# imu_shield.net
KiCad netlist of a schematic drawn in EAGLE
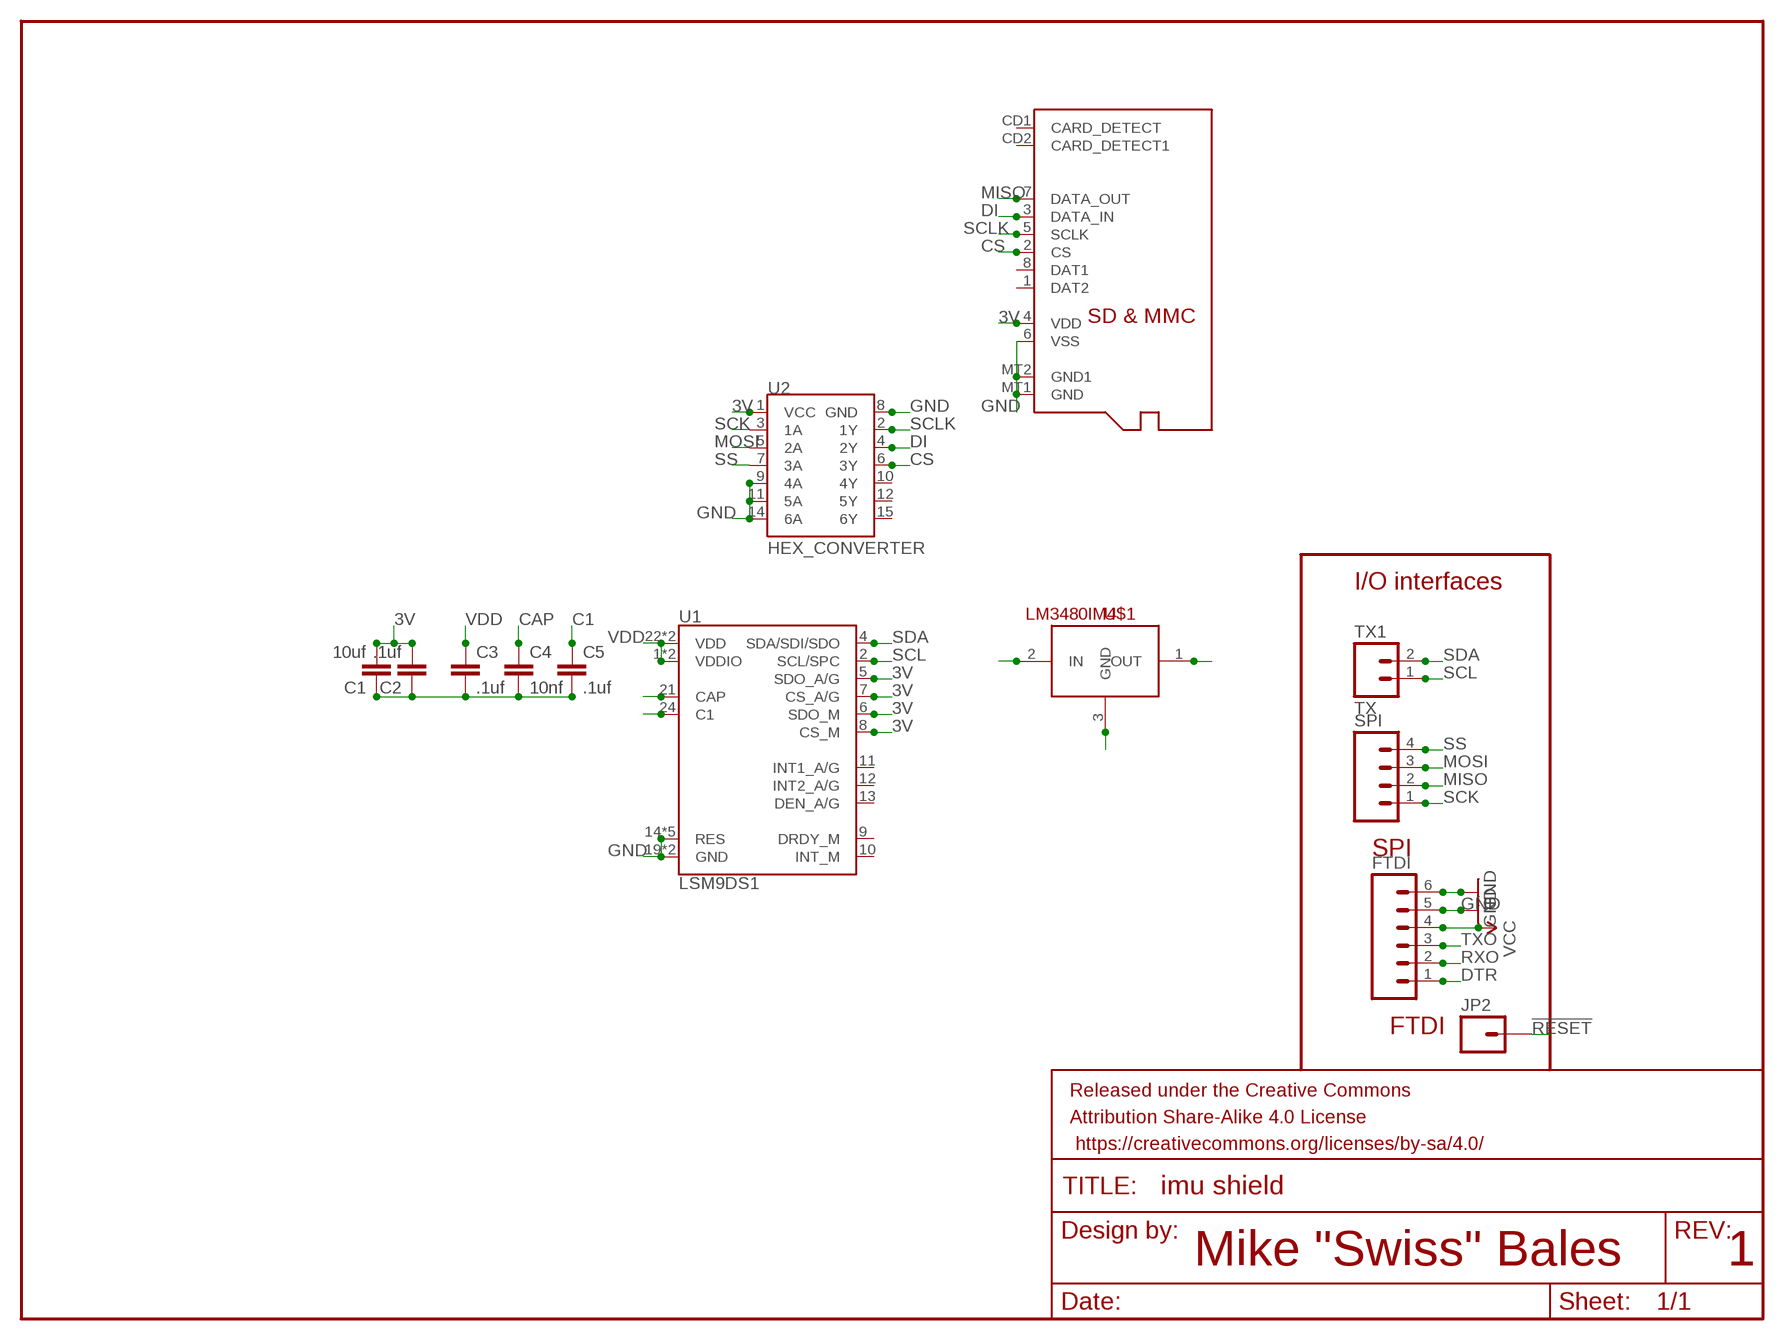
[diagram p0: schematic, sheet 1]

(export (version "E")
  (design (tool "Eeschema 10.0.6"))
  (components
    (comp (ref "C1")
      (value "10uf")
      (footprint "eagle-import:0805")
      (libsource (lib "eagle-import") (part "CAP0805"))
    )
    (comp (ref "C2")
      (value ".1uf")
      (footprint "eagle-import:0805")
      (libsource (lib "eagle-import") (part "CAP0805"))
    )
    (comp (ref "C3")
      (value ".1uf")
      (footprint "eagle-import:0805")
      (libsource (lib "eagle-import") (part "CAP0805"))
    )
    (comp (ref "C4")
      (value "10nf")
      (footprint "eagle-import:0805")
      (libsource (lib "eagle-import") (part "CAP0805"))
    )
    (comp (ref "C5")
      (value ".1uf")
      (footprint "eagle-import:0805")
      (libsource (lib "eagle-import") (part "CAP0805"))
    )
    (comp (ref "FRAME1")
      (value "FRAME-LETTER")
      (footprint "eagle-import:CREATIVE_COMMONS")
      (libsource (lib "eagle-import") (part "FRAME-LETTER"))
    )
    (comp (ref "FTDI")
      (value "M06NO_SILK_FEMALE_PTH")
      (footprint "eagle-import:1X06_NO_SILK")
      (libsource (lib "eagle-import") (part "M06NO_SILK_FEMALE_PTH"))
    )
    (comp (ref "JP2")
      (value "M01PTH")
      (footprint "eagle-import:1X01")
      (libsource (lib "eagle-import") (part "M01PTH"))
    )
    (comp (ref "SPI")
      (value "M04JST-PTH-VERT")
      (footprint "eagle-import:JST-4-PTH-VERT")
      (libsource (lib "eagle-import") (part "M04JST-PTH-VERT"))
    )
    (comp (ref "TX1")
      (value "TX")
      (footprint "eagle-import:JST-2-PTH-VERT")
      (libsource (lib "eagle-import") (part "M02JST-PTH-VERT"))
    )
    (comp (ref "U$1")
      (value "LM3480IM4")
      (footprint "eagle-import:SOT23-3")
      (libsource (lib "eagle-import") (part "LM3480IM4"))
    )
    (comp (ref "U$2")
      (value "MICROSD")
      (footprint "eagle-import:MICROSD")
      (libsource (lib "eagle-import") (part "MICROSD"))
    )
    (comp (ref "U1")
      (value "LSM9DS1")
      (footprint "eagle-import:LGA24-8X4")
      (libsource (lib "eagle-import") (part "LSM9DS1"))
    )
    (comp (ref "U2")
      (value "HEX_CONVERTER")
      (footprint "eagle-import:SO016")
      (libsource (lib "eagle-import") (part "HEX_CONVERTER"))
    )
  )
  (nets
    (net (code "1") (name "/3V") (class "Default")
      (node (ref "C1") (pin "2") (pinfunction "2_2") (pintype "passive"))
      (node (ref "C2") (pin "2") (pinfunction "2_2") (pintype "passive"))
      (node (ref "U$2") (pin "4") (pinfunction "VDD_4") (pintype "power_in"))
      (node (ref "U1") (pin "5") (pinfunction "SDO_A/G_5") (pintype "bidirectional"))
      (node (ref "U1") (pin "6") (pinfunction "SDO_M_6") (pintype "bidirectional"))
      (node (ref "U1") (pin "7") (pinfunction "CS_A/G_7") (pintype "bidirectional"))
      (node (ref "U1") (pin "8") (pinfunction "CS_M_8") (pintype "bidirectional"))
      (node (ref "U2") (pin "1") (pinfunction "VCC_1") (pintype "bidirectional"))
    )
    (net (code "2") (name "/C1") (class "Default")
      (node (ref "C5") (pin "1") (pinfunction "1_1") (pintype "passive"))
      (node (ref "U1") (pin "24") (pinfunction "C1_24") (pintype "bidirectional"))
    )
    (net (code "3") (name "/CAP") (class "Default")
      (node (ref "C4") (pin "1") (pinfunction "1_1") (pintype "passive"))
      (node (ref "U1") (pin "21") (pinfunction "CAP_21") (pintype "bidirectional"))
    )
    (net (code "4") (name "/CS") (class "Default")
      (node (ref "U$2") (pin "2") (pinfunction "CS_2") (pintype "input"))
      (node (ref "U2") (pin "6") (pinfunction "3Y_6") (pintype "bidirectional"))
    )
    (net (code "5") (name "/DI") (class "Default")
      (node (ref "U$2") (pin "3") (pinfunction "DATA_IN_3") (pintype "input"))
      (node (ref "U2") (pin "4") (pinfunction "2Y_4") (pintype "bidirectional"))
    )
    (net (code "6") (name "/DTR") (class "Default")
      (node (ref "FTDI") (pin "1") (pinfunction "1_1") (pintype "passive"))
    )
    (net (code "7") (name "/MISO") (class "Default")
      (node (ref "SPI") (pin "2") (pinfunction "2_2") (pintype "passive"))
      (node (ref "U$2") (pin "7") (pinfunction "DATA_OUT_7") (pintype "output"))
    )
    (net (code "8") (name "/MOSI") (class "Default")
      (node (ref "SPI") (pin "3") (pinfunction "3_3") (pintype "passive"))
      (node (ref "U2") (pin "5") (pinfunction "2A_5") (pintype "bidirectional"))
    )
    (net (code "9") (name "/RXO") (class "Default")
      (node (ref "FTDI") (pin "2") (pinfunction "2_2") (pintype "passive"))
    )
    (net (code "10") (name "/SCK") (class "Default")
      (node (ref "SPI") (pin "1") (pinfunction "1_1") (pintype "passive"))
      (node (ref "U2") (pin "3") (pinfunction "1A_3") (pintype "bidirectional"))
    )
    (net (code "11") (name "/SCL") (class "Default")
      (node (ref "TX1") (pin "1") (pinfunction "1_1") (pintype "passive"))
      (node (ref "U1") (pin "2") (pinfunction "SCL/SPC_2") (pintype "bidirectional"))
    )
    (net (code "12") (name "/SCLK") (class "Default")
      (node (ref "U$2") (pin "5") (pinfunction "SCLK_5") (pintype "input"))
      (node (ref "U2") (pin "2") (pinfunction "1Y_2") (pintype "bidirectional"))
    )
    (net (code "13") (name "/SDA") (class "Default")
      (node (ref "TX1") (pin "2") (pinfunction "2_2") (pintype "passive"))
      (node (ref "U1") (pin "4") (pinfunction "SDA/SDI/SDO_4") (pintype "bidirectional"))
    )
    (net (code "14") (name "/SS") (class "Default")
      (node (ref "SPI") (pin "4") (pinfunction "4_4") (pintype "passive"))
      (node (ref "U2") (pin "7") (pinfunction "3A_7") (pintype "bidirectional"))
    )
    (net (code "15") (name "/TXO") (class "Default")
      (node (ref "FTDI") (pin "3") (pinfunction "3_3") (pintype "passive"))
    )
    (net (code "16") (name "/VDD") (class "Default")
      (node (ref "C3") (pin "1") (pinfunction "1_1") (pintype "passive"))
      (node (ref "U$1") (pin "1") (pinfunction "OUT_1") (pintype "bidirectional"))
      (node (ref "U1") (pin "1") (pinfunction "VDDIO_1") (pintype "bidirectional"))
      (node (ref "U1") (pin "22") (pinfunction "VDD_22") (pintype "bidirectional"))
      (node (ref "U1") (pin "23") (pinfunction "VDD_23") (pintype "bidirectional"))
      (node (ref "U1") (pin "3") (pinfunction "VDDIO_3") (pintype "bidirectional"))
    )
    (net (code "17") (name "/~{RESET}") (class "Default")
      (node (ref "JP2") (pin "1") (pinfunction "1_1") (pintype "passive"))
    )
    (net (code "18") (name "GND") (class "Default")
      (node (ref "FTDI") (pin "5") (pinfunction "5_5") (pintype "passive"))
      (node (ref "FTDI") (pin "6") (pinfunction "6_6") (pintype "passive"))
      (node (ref "U$1") (pin "3") (pinfunction "GND_3") (pintype "bidirectional"))
      (node (ref "U$2") (pin "6") (pinfunction "VSS_6") (pintype "power_in"))
      (node (ref "U$2") (pin "MT1") (pinfunction "GND_MT1") (pintype "power_in"))
      (node (ref "U$2") (pin "MT2") (pinfunction "GND1_MT2") (pintype "power_in"))
      (node (ref "U1") (pin "14") (pinfunction "RES_14") (pintype "bidirectional"))
      (node (ref "U1") (pin "15") (pinfunction "RES_15") (pintype "bidirectional"))
      (node (ref "U1") (pin "16") (pinfunction "RES_16") (pintype "bidirectional"))
      (node (ref "U1") (pin "17") (pinfunction "RES_17") (pintype "bidirectional"))
      (node (ref "U1") (pin "18") (pinfunction "RES_18") (pintype "bidirectional"))
      (node (ref "U1") (pin "19") (pinfunction "GND_19") (pintype "bidirectional"))
      (node (ref "U1") (pin "20") (pinfunction "GND_20") (pintype "bidirectional"))
      (node (ref "U2") (pin "11") (pinfunction "5A_11") (pintype "bidirectional"))
      (node (ref "U2") (pin "14") (pinfunction "6A_14") (pintype "bidirectional"))
      (node (ref "U2") (pin "8") (pinfunction "GND_8") (pintype "bidirectional"))
      (node (ref "U2") (pin "9") (pinfunction "4A_9") (pintype "bidirectional"))
    )
    (net (code "19") (name "Net-(C1-Pad1)") (class "Default")
      (node (ref "C1") (pin "1") (pinfunction "1_1") (pintype "passive"))
      (node (ref "C2") (pin "1") (pinfunction "1_1") (pintype "passive"))
      (node (ref "C3") (pin "2") (pinfunction "2_2") (pintype "passive"))
      (node (ref "C4") (pin "2") (pinfunction "2_2") (pintype "passive"))
      (node (ref "C5") (pin "2") (pinfunction "2_2") (pintype "passive"))
    )
    (net (code "20") (name "VCC") (class "Default")
      (node (ref "FTDI") (pin "4") (pinfunction "4_4") (pintype "passive"))
      (node (ref "U$1") (pin "2") (pinfunction "IN_2") (pintype "bidirectional"))
    )
    (net (code "21") (name "unconnected-(U$2-CARD_DETECT-PadCD1)") (class "Default")
      (node (ref "U$2") (pin "CD1") (pinfunction "CARD_DETECT_CD1") (pintype "passive"))
    )
    (net (code "22") (name "unconnected-(U$2-CARD_DETECT1-PadCD2)") (class "Default")
      (node (ref "U$2") (pin "CD2") (pinfunction "CARD_DETECT1_CD2") (pintype "passive"))
    )
    (net (code "23") (name "unconnected-(U$2-DAT1-Pad8)") (class "Default")
      (node (ref "U$2") (pin "8") (pinfunction "DAT1_8") (pintype "bidirectional"))
    )
    (net (code "24") (name "unconnected-(U$2-DAT2-Pad1)") (class "Default")
      (node (ref "U$2") (pin "1") (pinfunction "DAT2_1") (pintype "bidirectional"))
    )
    (net (code "25") (name "unconnected-(U1-DEN_A{slash}G-Pad13)") (class "Default")
      (node (ref "U1") (pin "13") (pinfunction "DEN_A/G_13") (pintype "bidirectional"))
    )
    (net (code "26") (name "unconnected-(U1-DRDY_M-Pad9)") (class "Default")
      (node (ref "U1") (pin "9") (pinfunction "DRDY_M_9") (pintype "bidirectional"))
    )
    (net (code "27") (name "unconnected-(U1-INT1_A{slash}G-Pad11)") (class "Default")
      (node (ref "U1") (pin "11") (pinfunction "INT1_A/G_11") (pintype "bidirectional"))
    )
    (net (code "28") (name "unconnected-(U1-INT2_A{slash}G-Pad12)") (class "Default")
      (node (ref "U1") (pin "12") (pinfunction "INT2_A/G_12") (pintype "bidirectional"))
    )
    (net (code "29") (name "unconnected-(U1-INT_M-Pad10)") (class "Default")
      (node (ref "U1") (pin "10") (pinfunction "INT_M_10") (pintype "bidirectional"))
    )
    (net (code "30") (name "unconnected-(U2-4Y-Pad10)") (class "Default")
      (node (ref "U2") (pin "10") (pinfunction "4Y_10") (pintype "bidirectional"))
    )
    (net (code "31") (name "unconnected-(U2-5Y-Pad12)") (class "Default")
      (node (ref "U2") (pin "12") (pinfunction "5Y_12") (pintype "bidirectional"))
    )
    (net (code "32") (name "unconnected-(U2-6Y-Pad15)") (class "Default")
      (node (ref "U2") (pin "15") (pinfunction "6Y_15") (pintype "bidirectional"))
    )
  )
)
